# 06_-_Audio_In-Out.net
KiCad netlist of a schematic drawn in Altium Designer
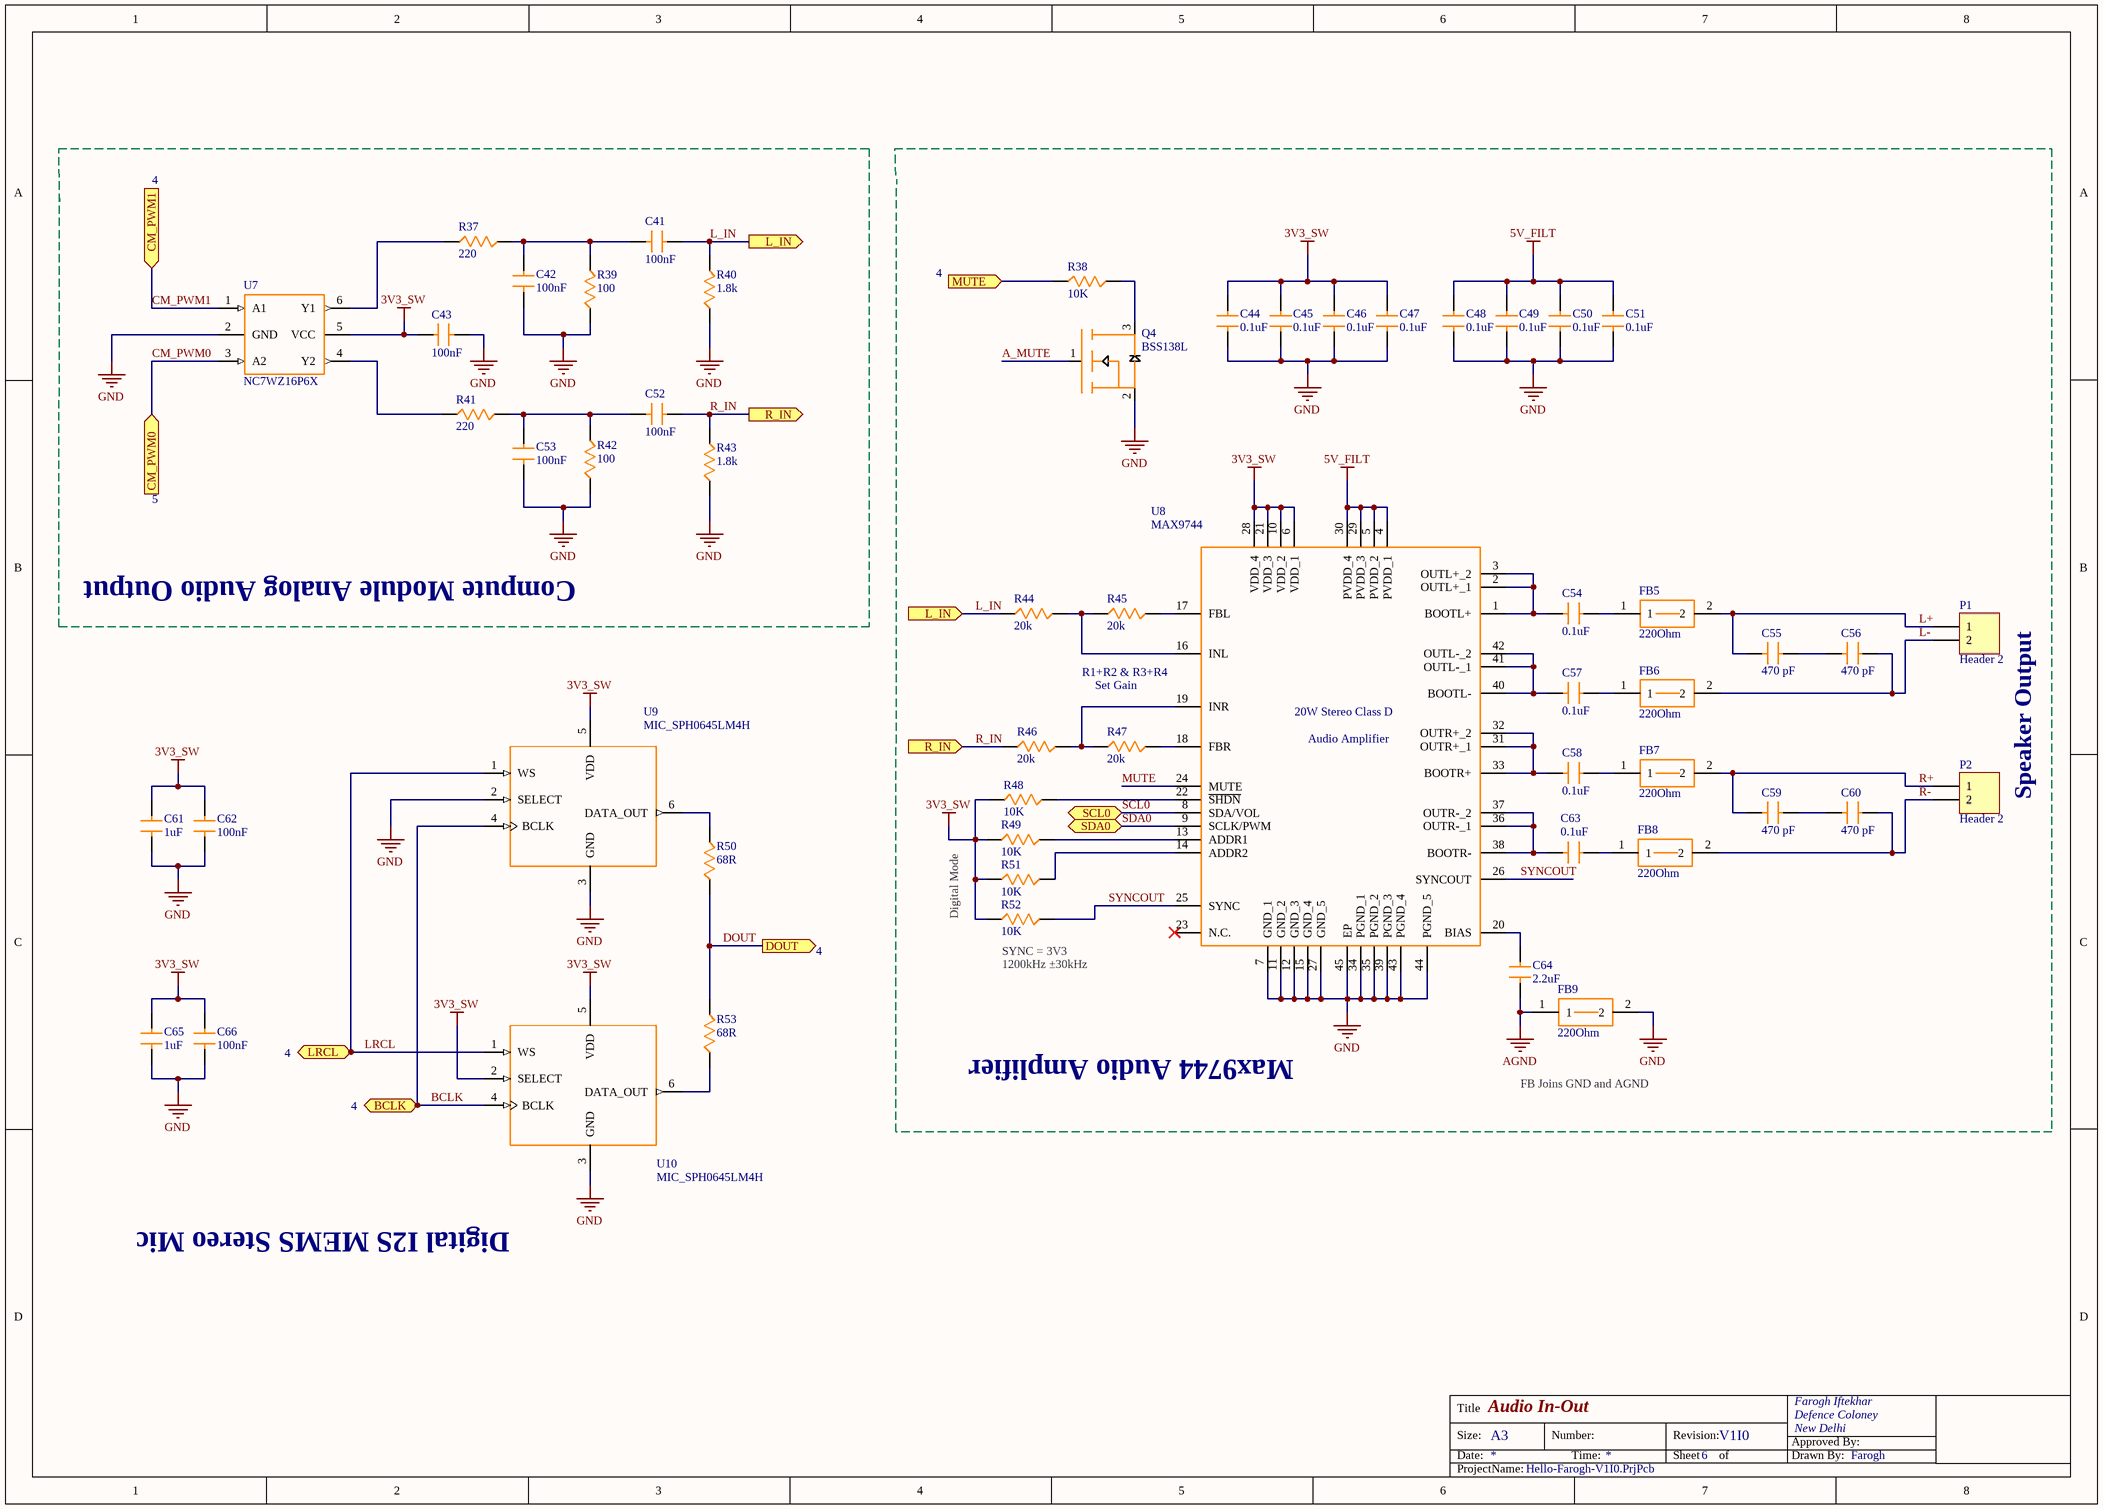
[diagram p0: [06] - Audio In-Out.SchDoc]

(export (version "E")
  (design (tool "Eeschema 10.0.6"))
  (components
    (comp (ref "C41")
      (value "100nF")
      (footprint "C0805")
      (description "Multilayer Ceramic Capacitors MLCC - SMD/SMT 100nF 16V 20% Ceramic Capacitor")
      (fields
        (field (name "MANUFACTURER") "Yageo")
        (field (name "MANUFACTURER PART NUMBER") "CC0805MRX7R7BB104")
      )
      (libsource (lib "Joule_Library") (part "C_0805-100nF-16V"))
    )
    (comp (ref "C42")
      (value "100nF")
      (footprint "C0805")
      (description "Multilayer Ceramic Capacitors MLCC - SMD/SMT 100nF 16V 20% Ceramic Capacitor")
      (fields
        (field (name "MANUFACTURER") "Yageo")
        (field (name "MANUFACTURER PART NUMBER") "CC0805MRX7R7BB104")
      )
      (libsource (lib "Joule_Library") (part "C_0805-100nF-16V"))
    )
    (comp (ref "C43")
      (value "100nF")
      (footprint "C0805")
      (description "Multilayer Ceramic Capacitors MLCC - SMD/SMT 100nF 16V 20% Ceramic Capacitor")
      (fields
        (field (name "MANUFACTURER") "Yageo")
        (field (name "MANUFACTURER PART NUMBER") "CC0805MRX7R7BB104")
      )
      (libsource (lib "Joule_Library") (part "C_0805-100nF-16V"))
    )
    (comp (ref "C44")
      (value "0.1uF")
      (footprint "C0805")
      (description "Multilayer Ceramic Capacitors MLCC - SMD/SMT 0.1uF 10% 50V AEC-Q200")
      (fields
        (field (name "MANUFACTURER") "Yageo")
        (field (name "MANUFACTURER PART NUMBER") "AS0805KKX7R9BB104")
      )
      (libsource (lib "Joule_Library") (part "C_0805-0.1uF"))
    )
    (comp (ref "C45")
      (value "0.1uF")
      (footprint "C0805")
      (description "Multilayer Ceramic Capacitors MLCC - SMD/SMT 0.1uF 10% 50V AEC-Q200")
      (fields
        (field (name "MANUFACTURER") "Yageo")
        (field (name "MANUFACTURER PART NUMBER") "AS0805KKX7R9BB104")
      )
      (libsource (lib "Joule_Library") (part "C_0805-0.1uF"))
    )
    (comp (ref "C46")
      (value "0.1uF")
      (footprint "C0805")
      (description "Multilayer Ceramic Capacitors MLCC - SMD/SMT 0.1uF 10% 50V AEC-Q200")
      (fields
        (field (name "MANUFACTURER") "Yageo")
        (field (name "MANUFACTURER PART NUMBER") "AS0805KKX7R9BB104")
      )
      (libsource (lib "Joule_Library") (part "C_0805-0.1uF"))
    )
    (comp (ref "C47")
      (value "0.1uF")
      (footprint "C0805")
      (description "Multilayer Ceramic Capacitors MLCC - SMD/SMT 0.1uF 10% 50V AEC-Q200")
      (fields
        (field (name "MANUFACTURER") "Yageo")
        (field (name "MANUFACTURER PART NUMBER") "AS0805KKX7R9BB104")
      )
      (libsource (lib "Joule_Library") (part "C_0805-0.1uF"))
    )
    (comp (ref "C48")
      (value "0.1uF")
      (footprint "C0805")
      (description "Multilayer Ceramic Capacitors MLCC - SMD/SMT 0.1uF 10% 50V AEC-Q200")
      (fields
        (field (name "MANUFACTURER") "Yageo")
        (field (name "MANUFACTURER PART NUMBER") "AS0805KKX7R9BB104")
      )
      (libsource (lib "Joule_Library") (part "C_0805-0.1uF"))
    )
    (comp (ref "C49")
      (value "0.1uF")
      (footprint "C0805")
      (description "Multilayer Ceramic Capacitors MLCC - SMD/SMT 0.1uF 10% 50V AEC-Q200")
      (fields
        (field (name "MANUFACTURER") "Yageo")
        (field (name "MANUFACTURER PART NUMBER") "AS0805KKX7R9BB104")
      )
      (libsource (lib "Joule_Library") (part "C_0805-0.1uF"))
    )
    (comp (ref "C50")
      (value "0.1uF")
      (footprint "C0805")
      (description "Multilayer Ceramic Capacitors MLCC - SMD/SMT 0.1uF 10% 50V AEC-Q200")
      (fields
        (field (name "MANUFACTURER") "Yageo")
        (field (name "MANUFACTURER PART NUMBER") "AS0805KKX7R9BB104")
      )
      (libsource (lib "Joule_Library") (part "C_0805-0.1uF"))
    )
    (comp (ref "C51")
      (value "0.1uF")
      (footprint "C0805")
      (description "Multilayer Ceramic Capacitors MLCC - SMD/SMT 0.1uF 10% 50V AEC-Q200")
      (fields
        (field (name "MANUFACTURER") "Yageo")
        (field (name "MANUFACTURER PART NUMBER") "AS0805KKX7R9BB104")
      )
      (libsource (lib "Joule_Library") (part "C_0805-0.1uF"))
    )
    (comp (ref "C52")
      (value "100nF")
      (footprint "C0805")
      (description "Multilayer Ceramic Capacitors MLCC - SMD/SMT 100nF 16V 20% Ceramic Capacitor")
      (fields
        (field (name "MANUFACTURER") "Yageo")
        (field (name "MANUFACTURER PART NUMBER") "CC0805MRX7R7BB104")
      )
      (libsource (lib "Joule_Library") (part "C_0805-100nF-16V"))
    )
    (comp (ref "C53")
      (value "100nF")
      (footprint "C0805")
      (description "Multilayer Ceramic Capacitors MLCC - SMD/SMT 100nF 16V 20% Ceramic Capacitor")
      (fields
        (field (name "MANUFACTURER") "Yageo")
        (field (name "MANUFACTURER PART NUMBER") "CC0805MRX7R7BB104")
      )
      (libsource (lib "Joule_Library") (part "C_0805-100nF-16V"))
    )
    (comp (ref "C54")
      (value "0.1uF")
      (footprint "C0805")
      (description "Multilayer Ceramic Capacitors MLCC - SMD/SMT 0.1uF 10% 50V AEC-Q200")
      (fields
        (field (name "MANUFACTURER") "Yageo")
        (field (name "MANUFACTURER PART NUMBER") "AS0805KKX7R9BB104")
      )
      (libsource (lib "Joule_Library") (part "C_0805-0.1uF"))
    )
    (comp (ref "C55")
      (value "470 pF")
      (footprint "C0805")
      (description "Multilayer Ceramic Capacitors MLCC - SMD/SMT 50V 470pF X7R 0805 10% AEC-Q200")
      (fields
        (field (name "MANUFACTURER") "KEMET")
        (field (name "MANUFACTURER PART NUMBER") "C0805S471K5RACAUTO")
      )
      (libsource (lib "Joule_Library") (part "C_0805-470 pF"))
    )
    (comp (ref "C56")
      (value "470 pF")
      (footprint "C0805")
      (description "Multilayer Ceramic Capacitors MLCC - SMD/SMT 50V 470pF X7R 0805 10% AEC-Q200")
      (fields
        (field (name "MANUFACTURER") "KEMET")
        (field (name "MANUFACTURER PART NUMBER") "C0805S471K5RACAUTO")
      )
      (libsource (lib "Joule_Library") (part "C_0805-470 pF"))
    )
    (comp (ref "C57")
      (value "0.1uF")
      (footprint "C0805")
      (description "Multilayer Ceramic Capacitors MLCC - SMD/SMT 0.1uF 10% 50V AEC-Q200")
      (fields
        (field (name "MANUFACTURER") "Yageo")
        (field (name "MANUFACTURER PART NUMBER") "AS0805KKX7R9BB104")
      )
      (libsource (lib "Joule_Library") (part "C_0805-0.1uF"))
    )
    (comp (ref "C58")
      (value "0.1uF")
      (footprint "C0805")
      (description "Multilayer Ceramic Capacitors MLCC - SMD/SMT 0.1uF 10% 50V AEC-Q200")
      (fields
        (field (name "MANUFACTURER") "Yageo")
        (field (name "MANUFACTURER PART NUMBER") "AS0805KKX7R9BB104")
      )
      (libsource (lib "Joule_Library") (part "C_0805-0.1uF"))
    )
    (comp (ref "C59")
      (value "470 pF")
      (footprint "C0805")
      (description "Multilayer Ceramic Capacitors MLCC - SMD/SMT 50V 470pF X7R 0805 10% AEC-Q200")
      (fields
        (field (name "MANUFACTURER") "KEMET")
        (field (name "MANUFACTURER PART NUMBER") "C0805S471K5RACAUTO")
      )
      (libsource (lib "Joule_Library") (part "C_0805-470 pF"))
    )
    (comp (ref "C60")
      (value "470 pF")
      (footprint "C0805")
      (description "Multilayer Ceramic Capacitors MLCC - SMD/SMT 50V 470pF X7R 0805 10% AEC-Q200")
      (fields
        (field (name "MANUFACTURER") "KEMET")
        (field (name "MANUFACTURER PART NUMBER") "C0805S471K5RACAUTO")
      )
      (libsource (lib "Joule_Library") (part "C_0805-470 pF"))
    )
    (comp (ref "C61")
      (value "1uF")
      (footprint "C0805")
      (description "Multilayer Ceramic Capacitors MLCC - SMD/SMT 10V 1uF X7R 0805 10%")
      (fields
        (field (name "MANUFACTURER") "KEMET")
        (field (name "MANUFACTURER PART NUMBER") "C0805C105K8RAC7210")
      )
      (libsource (lib "Joule_Library") (part "C_0805-1uF"))
    )
    (comp (ref "C62")
      (value "100nF")
      (footprint "C0805")
      (description "Multilayer Ceramic Capacitors MLCC - SMD/SMT 100nF 16V 20% Ceramic Capacitor")
      (fields
        (field (name "MANUFACTURER") "Yageo")
        (field (name "MANUFACTURER PART NUMBER") "CC0805MRX7R7BB104")
      )
      (libsource (lib "Joule_Library") (part "C_0805-100nF-16V"))
    )
    (comp (ref "C63")
      (value "0.1uF")
      (footprint "C0805")
      (description "Multilayer Ceramic Capacitors MLCC - SMD/SMT 0.1uF 10% 50V AEC-Q200")
      (fields
        (field (name "MANUFACTURER") "Yageo")
        (field (name "MANUFACTURER PART NUMBER") "AS0805KKX7R9BB104")
      )
      (libsource (lib "Joule_Library") (part "C_0805-0.1uF"))
    )
    (comp (ref "C64")
      (value "2.2uF")
      (footprint "C1206")
      (description "Multilayer Ceramic Capacitors MLCC - SMD/SMT 25V 2.2uF X7R 1206 10%")
      (fields
        (field (name "MANUFACTURER") "KEMET")
        (field (name "MANUFACTURER PART NUMBER") "C1206C225K3REC7210")
      )
      (libsource (lib "Joule_Library") (part "C_1206-2.2uF"))
    )
    (comp (ref "C65")
      (value "1uF")
      (footprint "C0805")
      (description "Multilayer Ceramic Capacitors MLCC - SMD/SMT 10V 1uF X7R 0805 10%")
      (fields
        (field (name "MANUFACTURER") "KEMET")
        (field (name "MANUFACTURER PART NUMBER") "C0805C105K8RAC7210")
      )
      (libsource (lib "Joule_Library") (part "C_0805-1uF"))
    )
    (comp (ref "C66")
      (value "100nF")
      (footprint "C0805")
      (description "Multilayer Ceramic Capacitors MLCC - SMD/SMT 100nF 16V 20% Ceramic Capacitor")
      (fields
        (field (name "MANUFACTURER") "Yageo")
        (field (name "MANUFACTURER PART NUMBER") "CC0805MRX7R7BB104")
      )
      (libsource (lib "Joule_Library") (part "C_0805-100nF-16V"))
    )
    (comp (ref "FB5")
      (value "220Ohm")
      (footprint "FB_0805")
      (description "Ferrite Beads NEW MFG PN 810-MPZ2012S221AT000")
      (fields (field (name "MANUFACTURER") "TDK") (field (name "MANUFACTURER PART NUMBER") "MPZ2012S221A"))
      (libsource (lib "Joule_Library") (part "FB_0805-220, 3000mA"))
    )
    (comp (ref "FB6")
      (value "220Ohm")
      (footprint "FB_0805")
      (description "Ferrite Beads NEW MFG PN 810-MPZ2012S221AT000")
      (fields (field (name "MANUFACTURER") "TDK") (field (name "MANUFACTURER PART NUMBER") "MPZ2012S221A"))
      (libsource (lib "Joule_Library") (part "FB_0805-220, 3000mA"))
    )
    (comp (ref "FB7")
      (value "220Ohm")
      (footprint "FB_0805")
      (description "Ferrite Beads NEW MFG PN 810-MPZ2012S221AT000")
      (fields (field (name "MANUFACTURER") "TDK") (field (name "MANUFACTURER PART NUMBER") "MPZ2012S221A"))
      (libsource (lib "Joule_Library") (part "FB_0805-220, 3000mA"))
    )
    (comp (ref "FB8")
      (value "220Ohm")
      (footprint "FB_0805")
      (description "Ferrite Beads NEW MFG PN 810-MPZ2012S221AT000")
      (fields (field (name "MANUFACTURER") "TDK") (field (name "MANUFACTURER PART NUMBER") "MPZ2012S221A"))
      (libsource (lib "Joule_Library") (part "FB_0805-220, 3000mA"))
    )
    (comp (ref "FB9")
      (value "220Ohm")
      (footprint "FB_0805")
      (description "Ferrite Beads NEW MFG PN 810-MPZ2012S221AT000")
      (fields (field (name "MANUFACTURER") "TDK") (field (name "MANUFACTURER PART NUMBER") "MPZ2012S221A"))
      (libsource (lib "Joule_Library") (part "FB_0805-220, 3000mA"))
    )
    (comp (ref "P1")
      (value "Header 2")
      (footprint "HDR1X2")
      (description "Header, 2-Pin")
      (fields (field (name "PUBLISHER") "Altium Limited"))
      (libsource (lib "Miscellaneous Connectors") (part "Header 2"))
    )
    (comp (ref "P2")
      (value "Header 2")
      (footprint "HDR1X2")
      (description "Header, 2-Pin")
      (fields (field (name "PUBLISHER") "Altium Limited"))
      (libsource (lib "Miscellaneous Connectors") (part "Header 2"))
    )
    (comp (ref "Q4")
      (value "BSS138L")
      (footprint "BVSS138L")
      (description "MOSFET FET 50V 3.5 OHM SOT23")
      (fields (field (name "MANUFACTURER") "ON Semiconductor / Fairchild"))
      (libsource (lib "Joule_Library") (part "BSS138L"))
    )
    (comp (ref "R37")
      (value "220")
      (footprint "R0805")
      (description "Thin Film Resistors - SMD")
      (fields
        (field (name "MANUFACTURER") "Yageo")
        (field (name "MANUFACTURER PART NUMBER") "RT0805DRE07220RL")
      )
      (libsource (lib "Joule_Library") (part "R_0805-220"))
    )
    (comp (ref "R38")
      (value "10K")
      (footprint "R0805")
      (description "Thick Film Resistors - SMD 10K   OHM   1% 1/4W")
      (fields
        (field (name "MANUFACTURER") "Yageo")
        (field (name "MANUFACTURER PART NUMBER") "RC0805FR-7W10KL")
      )
      (libsource (lib "Joule_Library") (part "R_0805-10K"))
    )
    (comp (ref "R39")
      (value "100")
      (footprint "R0805")
      (description "Thin Film Resistors - SMD 100Ohm,0805,1%,25ppm ,100mW,100V")
      (fields
        (field (name "MANUFACTURER") "KOA Speer")
        (field (name "MANUFACTURER PART NUMBER") "RN732ATTDK1000F25")
      )
      (libsource (lib "Joule_Library") (part "R_0805-100"))
    )
    (comp (ref "R40")
      (value "1.8k")
      (footprint "R0805")
      (description "Thin Film Resistors - SMD")
      (fields
        (field (name "MANUFACTURER") "Yageo")
        (field (name "MANUFACTURER PART NUMBER") "RT0805CRE071K8L")
      )
      (libsource (lib "Joule_Library") (part "R_0805-1.8K"))
    )
    (comp (ref "R41")
      (value "220")
      (footprint "R0805")
      (description "Thin Film Resistors - SMD")
      (fields
        (field (name "MANUFACTURER") "Yageo")
        (field (name "MANUFACTURER PART NUMBER") "RT0805DRE07220RL")
      )
      (libsource (lib "Joule_Library") (part "R_0805-220"))
    )
    (comp (ref "R42")
      (value "100")
      (footprint "R0805")
      (description "Thin Film Resistors - SMD 100Ohm,0805,1%,25ppm ,100mW,100V")
      (fields
        (field (name "MANUFACTURER") "KOA Speer")
        (field (name "MANUFACTURER PART NUMBER") "RN732ATTDK1000F25")
      )
      (libsource (lib "Joule_Library") (part "R_0805-100"))
    )
    (comp (ref "R43")
      (value "1.8k")
      (footprint "R0805")
      (description "Thin Film Resistors - SMD")
      (fields
        (field (name "MANUFACTURER") "Yageo")
        (field (name "MANUFACTURER PART NUMBER") "RT0805CRE071K8L")
      )
      (libsource (lib "Joule_Library") (part "R_0805-1.8K"))
    )
    (comp (ref "R44")
      (value "20k")
      (footprint "R0805")
      (description "Thin Film Resistors - SMD 20 Kohms 0.1% Tol. AEC-Q200")
      (fields
        (field (name "MANUFACTURER") "Yageo")
        (field (name "MANUFACTURER PART NUMBER") "AT0805BRD0720KL")
      )
      (libsource (lib "Joule_Library") (part "R_0805-20K"))
    )
    (comp (ref "R45")
      (value "20k")
      (footprint "R0805")
      (description "Thin Film Resistors - SMD 20 Kohms 0.1% Tol. AEC-Q200")
      (fields
        (field (name "MANUFACTURER") "Yageo")
        (field (name "MANUFACTURER PART NUMBER") "AT0805BRD0720KL")
      )
      (libsource (lib "Joule_Library") (part "R_0805-20K"))
    )
    (comp (ref "R46")
      (value "20k")
      (footprint "R0805")
      (description "Thin Film Resistors - SMD 20 Kohms 0.1% Tol. AEC-Q200")
      (fields
        (field (name "MANUFACTURER") "Yageo")
        (field (name "MANUFACTURER PART NUMBER") "AT0805BRD0720KL")
      )
      (libsource (lib "Joule_Library") (part "R_0805-20K"))
    )
    (comp (ref "R47")
      (value "20k")
      (footprint "R0805")
      (description "Thin Film Resistors - SMD 20 Kohms 0.1% Tol. AEC-Q200")
      (fields
        (field (name "MANUFACTURER") "Yageo")
        (field (name "MANUFACTURER PART NUMBER") "AT0805BRD0720KL")
      )
      (libsource (lib "Joule_Library") (part "R_0805-20K"))
    )
    (comp (ref "R48")
      (value "10K")
      (footprint "R0805")
      (description "Thick Film Resistors - SMD 10K   OHM   1% 1/4W")
      (fields
        (field (name "MANUFACTURER") "Yageo")
        (field (name "MANUFACTURER PART NUMBER") "RC0805FR-7W10KL")
      )
      (libsource (lib "Joule_Library") (part "R_0805-10K"))
    )
    (comp (ref "R49")
      (value "10K")
      (footprint "R0805")
      (description "Thick Film Resistors - SMD 10K   OHM   1% 1/4W")
      (fields
        (field (name "MANUFACTURER") "Yageo")
        (field (name "MANUFACTURER PART NUMBER") "RC0805FR-7W10KL")
      )
      (libsource (lib "Joule_Library") (part "R_0805-10K"))
    )
    (comp (ref "R50")
      (value "68R")
      (footprint "R0805")
      (description "Thick Film Resistors - SMD 1/8Watt 68ohms 1% Commercial Use")
      (fields
        (field (name "MANUFACTURER") "Vishay / Dale")
        (field (name "MANUFACTURER PART NUMBER") "CRCW080568R0FKEAC")
      )
      (libsource (lib "Joule_Library") (part "R_0805-68R"))
    )
    (comp (ref "R51")
      (value "10K")
      (footprint "R0805")
      (description "Thick Film Resistors - SMD 10K   OHM   1% 1/4W")
      (fields
        (field (name "MANUFACTURER") "Yageo")
        (field (name "MANUFACTURER PART NUMBER") "RC0805FR-7W10KL")
      )
      (libsource (lib "Joule_Library") (part "R_0805-10K"))
    )
    (comp (ref "R52")
      (value "10K")
      (footprint "R0805")
      (description "Thick Film Resistors - SMD 10K   OHM   1% 1/4W")
      (fields
        (field (name "MANUFACTURER") "Yageo")
        (field (name "MANUFACTURER PART NUMBER") "RC0805FR-7W10KL")
      )
      (libsource (lib "Joule_Library") (part "R_0805-10K"))
    )
    (comp (ref "R53")
      (value "68R")
      (footprint "R0805")
      (description "Thick Film Resistors - SMD 1/8Watt 68ohms 1% Commercial Use")
      (fields
        (field (name "MANUFACTURER") "Vishay / Dale")
        (field (name "MANUFACTURER PART NUMBER") "CRCW080568R0FKEAC")
      )
      (libsource (lib "Joule_Library") (part "R_0805-68R"))
    )
    (comp (ref "U7")
      (value "NC7WZ16P6X")
      (footprint "SOT65P210X110-6N")
      (description "Buffers & Line Drivers UHS Dual Buffer")
      (fields (field (name "MANUFACTURER") "ON Semiconductor / Fairchild"))
      (libsource (lib "Joule_Library") (part "NC7WZ16P6X"))
    )
    (comp (ref "U8")
      (value "MAX9744")
      (footprint "QFN50P700X700X80-45N")
      (description "Audio Amplifiers Stereo 20W Class D Amplifier")
      (fields
        (field (name "MANUFACTURER") "Maxim Integrated")
        (field (name "MANUFACTURER PART NUMBER") "MAX9744ETH+T")
      )
      (libsource (lib "Joule_Library") (part "MAX9744ETH+T"))
    )
    (comp (ref "U9")
      (value "MIC_SPH0645LM4H")
      (footprint "SPH0645LM4H-B")
      (description "MEMS Microphones DIG MEMs Mic, BP w/ I2S output")
      (fields
        (field (name "MANUFACTURER") "Knowles")
        (field (name "MANUFACTURER PART NUMBER") "SPH0645LM4H-B")
      )
      (libsource (lib "Joule_Library") (part "MIC_SPH0645LM4H-B"))
    )
    (comp (ref "U10")
      (value "MIC_SPH0645LM4H")
      (footprint "SPH0645LM4H-B")
      (description "MEMS Microphones DIG MEMs Mic, BP w/ I2S output")
      (fields
        (field (name "MANUFACTURER") "Knowles")
        (field (name "MANUFACTURER PART NUMBER") "SPH0645LM4H-B")
      )
      (libsource (lib "Joule_Library") (part "MIC_SPH0645LM4H-B"))
    )
  )
  (nets
    (net (code "1") (name "/A_MUTE") (class "Default")
      (node (ref "Q4") (pin "1") (pinfunction "G_1") (pintype "passive"))
    )
    (net (code "2") (name "/BCLK") (class "Default")
      (node (ref "U10") (pin "4") (pinfunction "BCLK_4") (pintype "input"))
      (node (ref "U9") (pin "4") (pinfunction "BCLK_4") (pintype "input"))
    )
    (net (code "3") (name "/CM_PWM0") (class "Default")
      (node (ref "U7") (pin "3") (pinfunction "A2_3") (pintype "input"))
    )
    (net (code "4") (name "/CM_PWM1") (class "Default")
      (node (ref "U7") (pin "1") (pinfunction "A1_1") (pintype "input"))
    )
    (net (code "5") (name "/DOUT") (class "Default")
      (node (ref "R50") (pin "1") (pinfunction "1_1") (pintype "passive"))
      (node (ref "R53") (pin "2") (pinfunction "2_2") (pintype "passive"))
    )
    (net (code "6") (name "/L+") (class "Default")
      (node (ref "C55") (pin "1") (pinfunction "1_1") (pintype "passive"))
      (node (ref "FB5") (pin "2") (pinfunction "2_2") (pintype "passive"))
      (node (ref "P1") (pin "1") (pinfunction "1_1") (pintype "passive"))
    )
    (net (code "7") (name "/L-") (class "Default")
      (node (ref "C56") (pin "2") (pinfunction "2_2") (pintype "passive"))
      (node (ref "FB6") (pin "2") (pinfunction "2_2") (pintype "passive"))
      (node (ref "P1") (pin "2") (pinfunction "2_2") (pintype "passive"))
    )
    (net (code "8") (name "/LRCL") (class "Default")
      (node (ref "U10") (pin "1") (pinfunction "WS_1") (pintype "input"))
      (node (ref "U9") (pin "1") (pinfunction "WS_1") (pintype "input"))
    )
    (net (code "9") (name "/L_IN") (class "Default")
      (node (ref "C41") (pin "2") (pinfunction "2_2") (pintype "passive"))
      (node (ref "R40") (pin "2") (pinfunction "2_2") (pintype "passive"))
      (node (ref "R44") (pin "1") (pinfunction "1_1") (pintype "passive"))
    )
    (net (code "10") (name "/MUTE") (class "Default")
      (node (ref "R38") (pin "2") (pinfunction "2_2") (pintype "passive"))
      (node (ref "U8") (pin "24") (pinfunction "MUTE_24") (pintype "passive"))
    )
    (net (code "11") (name "/R+") (class "Default")
      (node (ref "C59") (pin "1") (pinfunction "1_1") (pintype "passive"))
      (node (ref "FB7") (pin "2") (pinfunction "2_2") (pintype "passive"))
      (node (ref "P2") (pin "1") (pinfunction "1_1") (pintype "passive"))
    )
    (net (code "12") (name "/R-") (class "Default")
      (node (ref "C60") (pin "2") (pinfunction "2_2") (pintype "passive"))
      (node (ref "FB8") (pin "2") (pinfunction "2_2") (pintype "passive"))
      (node (ref "P2") (pin "2") (pinfunction "2_2") (pintype "passive"))
    )
    (net (code "13") (name "/R_IN") (class "Default")
      (node (ref "C52") (pin "2") (pinfunction "2_2") (pintype "passive"))
      (node (ref "R43") (pin "2") (pinfunction "2_2") (pintype "passive"))
      (node (ref "R46") (pin "1") (pinfunction "1_1") (pintype "passive"))
    )
    (net (code "14") (name "/SCL0") (class "Default")
      (node (ref "U8") (pin "8") (pinfunction "SDA/VOL_8") (pintype "passive"))
    )
    (net (code "15") (name "/SDA0") (class "Default")
      (node (ref "U8") (pin "9") (pinfunction "SCLK/PWM_9") (pintype "passive"))
    )
    (net (code "16") (name "/SYNCOUT") (class "Default")
      (node (ref "R52") (pin "1") (pinfunction "1_1") (pintype "passive"))
      (node (ref "U8") (pin "25") (pinfunction "SYNC_25") (pintype "passive"))
      (node (ref "U8") (pin "26") (pinfunction "SYNCOUT_26") (pintype "passive"))
    )
    (net (code "17") (name "3V3_SW") (class "Default")
      (node (ref "C43") (pin "2") (pinfunction "2_2") (pintype "passive"))
      (node (ref "C44") (pin "2") (pinfunction "2_2") (pintype "passive"))
      (node (ref "C45") (pin "2") (pinfunction "2_2") (pintype "passive"))
      (node (ref "C46") (pin "2") (pinfunction "2_2") (pintype "passive"))
      (node (ref "C47") (pin "2") (pinfunction "2_2") (pintype "passive"))
      (node (ref "C61") (pin "2") (pinfunction "2_2") (pintype "passive"))
      (node (ref "C62") (pin "2") (pinfunction "2_2") (pintype "passive"))
      (node (ref "C65") (pin "2") (pinfunction "2_2") (pintype "passive"))
      (node (ref "C66") (pin "2") (pinfunction "2_2") (pintype "passive"))
      (node (ref "R48") (pin "2") (pinfunction "2_2") (pintype "passive"))
      (node (ref "R49") (pin "2") (pinfunction "2_2") (pintype "passive"))
      (node (ref "R51") (pin "2") (pinfunction "2_2") (pintype "passive"))
      (node (ref "R52") (pin "2") (pinfunction "2_2") (pintype "passive"))
      (node (ref "U10") (pin "2") (pinfunction "SELECT_2") (pintype "input"))
      (node (ref "U10") (pin "5") (pinfunction "VDD_5") (pintype "power_in"))
      (node (ref "U7") (pin "5") (pinfunction "VCC_5") (pintype "power_in"))
      (node (ref "U8") (pin "10") (pinfunction "VDD_2_10") (pintype "passive"))
      (node (ref "U8") (pin "21") (pinfunction "VDD_3_21") (pintype "passive"))
      (node (ref "U8") (pin "28") (pinfunction "VDD_4_28") (pintype "passive"))
      (node (ref "U8") (pin "6") (pinfunction "VDD_1_6") (pintype "passive"))
      (node (ref "U9") (pin "5") (pinfunction "VDD_5") (pintype "power_in"))
    )
    (net (code "18") (name "5V_FILT") (class "Default")
      (node (ref "C48") (pin "2") (pinfunction "2_2") (pintype "passive"))
      (node (ref "C49") (pin "2") (pinfunction "2_2") (pintype "passive"))
      (node (ref "C50") (pin "2") (pinfunction "2_2") (pintype "passive"))
      (node (ref "C51") (pin "2") (pinfunction "2_2") (pintype "passive"))
      (node (ref "U8") (pin "29") (pinfunction "PVDD_3_29") (pintype "passive"))
      (node (ref "U8") (pin "30") (pinfunction "PVDD_4_30") (pintype "passive"))
      (node (ref "U8") (pin "4") (pinfunction "PVDD_1_4") (pintype "passive"))
      (node (ref "U8") (pin "5") (pinfunction "PVDD_2_5") (pintype "passive"))
    )
    (net (code "19") (name "AGND") (class "Default")
      (node (ref "C64") (pin "1") (pinfunction "1_1") (pintype "passive"))
      (node (ref "FB9") (pin "1") (pinfunction "1_1") (pintype "passive"))
    )
    (net (code "20") (name "GND") (class "Default")
      (node (ref "C42") (pin "1") (pinfunction "1_1") (pintype "passive"))
      (node (ref "C43") (pin "1") (pinfunction "1_1") (pintype "passive"))
      (node (ref "C44") (pin "1") (pinfunction "1_1") (pintype "passive"))
      (node (ref "C45") (pin "1") (pinfunction "1_1") (pintype "passive"))
      (node (ref "C46") (pin "1") (pinfunction "1_1") (pintype "passive"))
      (node (ref "C47") (pin "1") (pinfunction "1_1") (pintype "passive"))
      (node (ref "C48") (pin "1") (pinfunction "1_1") (pintype "passive"))
      (node (ref "C49") (pin "1") (pinfunction "1_1") (pintype "passive"))
      (node (ref "C50") (pin "1") (pinfunction "1_1") (pintype "passive"))
      (node (ref "C51") (pin "1") (pinfunction "1_1") (pintype "passive"))
      (node (ref "C53") (pin "1") (pinfunction "1_1") (pintype "passive"))
      (node (ref "C61") (pin "1") (pinfunction "1_1") (pintype "passive"))
      (node (ref "C62") (pin "1") (pinfunction "1_1") (pintype "passive"))
      (node (ref "C65") (pin "1") (pinfunction "1_1") (pintype "passive"))
      (node (ref "C66") (pin "1") (pinfunction "1_1") (pintype "passive"))
      (node (ref "FB9") (pin "2") (pinfunction "2_2") (pintype "passive"))
      (node (ref "Q4") (pin "2") (pinfunction "S_2") (pintype "passive"))
      (node (ref "R39") (pin "1") (pinfunction "1_1") (pintype "passive"))
      (node (ref "R40") (pin "1") (pinfunction "1_1") (pintype "passive"))
      (node (ref "R42") (pin "1") (pinfunction "1_1") (pintype "passive"))
      (node (ref "R43") (pin "1") (pinfunction "1_1") (pintype "passive"))
      (node (ref "U10") (pin "3") (pinfunction "GND_3") (pintype "power_in"))
      (node (ref "U7") (pin "2") (pinfunction "GND_2") (pintype "power_in"))
      (node (ref "U8") (pin "11") (pinfunction "GND_2_11") (pintype "passive"))
      (node (ref "U8") (pin "12") (pinfunction "GND_3_12") (pintype "passive"))
      (node (ref "U8") (pin "15") (pinfunction "GND_4_15") (pintype "passive"))
      (node (ref "U8") (pin "27") (pinfunction "GND_5_27") (pintype "passive"))
      (node (ref "U8") (pin "34") (pinfunction "PGND_1_34") (pintype "passive"))
      (node (ref "U8") (pin "35") (pinfunction "PGND_2_35") (pintype "passive"))
      (node (ref "U8") (pin "39") (pinfunction "PGND_3_39") (pintype "passive"))
      (node (ref "U8") (pin "43") (pinfunction "PGND_4_43") (pintype "passive"))
      (node (ref "U8") (pin "44") (pinfunction "PGND_5_44") (pintype "passive"))
      (node (ref "U8") (pin "45") (pinfunction "EP_45") (pintype "passive"))
      (node (ref "U8") (pin "7") (pinfunction "GND_1_7") (pintype "passive"))
      (node (ref "U9") (pin "2") (pinfunction "SELECT_2") (pintype "input"))
      (node (ref "U9") (pin "3") (pinfunction "GND_3") (pintype "power_in"))
    )
    (net (code "21") (name "Net-(C41-Pad1)") (class "Default")
      (node (ref "C41") (pin "1") (pinfunction "1_1") (pintype "passive"))
      (node (ref "C42") (pin "2") (pinfunction "2_2") (pintype "passive"))
      (node (ref "R37") (pin "2") (pinfunction "2_2") (pintype "passive"))
      (node (ref "R39") (pin "2") (pinfunction "2_2") (pintype "passive"))
    )
    (net (code "22") (name "Net-(C52-Pad1)") (class "Default")
      (node (ref "C52") (pin "1") (pinfunction "1_1") (pintype "passive"))
      (node (ref "C53") (pin "2") (pinfunction "2_2") (pintype "passive"))
      (node (ref "R41") (pin "2") (pinfunction "2_2") (pintype "passive"))
      (node (ref "R42") (pin "2") (pinfunction "2_2") (pintype "passive"))
    )
    (net (code "23") (name "Net-(C54-Pad2)") (class "Default")
      (node (ref "C54") (pin "2") (pinfunction "2_2") (pintype "passive"))
      (node (ref "FB5") (pin "1") (pinfunction "1_1") (pintype "passive"))
    )
    (net (code "24") (name "Net-(C55-Pad2)") (class "Default")
      (node (ref "C55") (pin "2") (pinfunction "2_2") (pintype "passive"))
      (node (ref "C56") (pin "1") (pinfunction "1_1") (pintype "passive"))
    )
    (net (code "25") (name "Net-(C57-Pad2)") (class "Default")
      (node (ref "C57") (pin "2") (pinfunction "2_2") (pintype "passive"))
      (node (ref "FB6") (pin "1") (pinfunction "1_1") (pintype "passive"))
    )
    (net (code "26") (name "Net-(C58-Pad2)") (class "Default")
      (node (ref "C58") (pin "2") (pinfunction "2_2") (pintype "passive"))
      (node (ref "FB7") (pin "1") (pinfunction "1_1") (pintype "passive"))
    )
    (net (code "27") (name "Net-(C59-Pad2)") (class "Default")
      (node (ref "C59") (pin "2") (pinfunction "2_2") (pintype "passive"))
      (node (ref "C60") (pin "1") (pinfunction "1_1") (pintype "passive"))
    )
    (net (code "28") (name "Net-(C63-Pad2)") (class "Default")
      (node (ref "C63") (pin "2") (pinfunction "2_2") (pintype "passive"))
      (node (ref "FB8") (pin "1") (pinfunction "1_1") (pintype "passive"))
    )
    (net (code "29") (name "Net-(Q4-D)") (class "Default")
      (node (ref "Q4") (pin "3") (pinfunction "D_3") (pintype "passive"))
      (node (ref "R38") (pin "1") (pinfunction "1_1") (pintype "passive"))
    )
    (net (code "30") (name "Net-(U7-Y1)") (class "Default")
      (node (ref "R37") (pin "1") (pinfunction "1_1") (pintype "passive"))
      (node (ref "U7") (pin "6") (pinfunction "Y1_6") (pintype "output"))
    )
    (net (code "31") (name "Net-(U7-Y2)") (class "Default")
      (node (ref "R41") (pin "1") (pinfunction "1_1") (pintype "passive"))
      (node (ref "U7") (pin "4") (pinfunction "Y2_4") (pintype "output"))
    )
    (net (code "32") (name "Net-(U8-ADDR1)") (class "Default")
      (node (ref "R49") (pin "1") (pinfunction "1_1") (pintype "passive"))
      (node (ref "U8") (pin "13") (pinfunction "ADDR1_13") (pintype "passive"))
    )
    (net (code "33") (name "Net-(U8-ADDR2)") (class "Default")
      (node (ref "R51") (pin "1") (pinfunction "1_1") (pintype "passive"))
      (node (ref "U8") (pin "14") (pinfunction "ADDR2_14") (pintype "passive"))
    )
    (net (code "34") (name "Net-(U8-BIAS)") (class "Default")
      (node (ref "C64") (pin "2") (pinfunction "2_2") (pintype "passive"))
      (node (ref "U8") (pin "20") (pinfunction "BIAS_20") (pintype "passive"))
    )
    (net (code "35") (name "Net-(U8-BOOTL+)") (class "Default")
      (node (ref "C54") (pin "1") (pinfunction "1_1") (pintype "passive"))
      (node (ref "U8") (pin "1") (pinfunction "BOOTL+_1") (pintype "passive"))
      (node (ref "U8") (pin "2") (pinfunction "OUTL+_1_2") (pintype "passive"))
      (node (ref "U8") (pin "3") (pinfunction "OUTL+_2_3") (pintype "passive"))
    )
    (net (code "36") (name "Net-(U8-BOOTL-)") (class "Default")
      (node (ref "C57") (pin "1") (pinfunction "1_1") (pintype "passive"))
      (node (ref "U8") (pin "40") (pinfunction "BOOTL-_40") (pintype "passive"))
      (node (ref "U8") (pin "41") (pinfunction "OUTL-_1_41") (pintype "passive"))
      (node (ref "U8") (pin "42") (pinfunction "OUTL-_2_42") (pintype "passive"))
    )
    (net (code "37") (name "Net-(U8-BOOTR+)") (class "Default")
      (node (ref "C58") (pin "1") (pinfunction "1_1") (pintype "passive"))
      (node (ref "U8") (pin "31") (pinfunction "OUTR+_1_31") (pintype "passive"))
      (node (ref "U8") (pin "32") (pinfunction "OUTR+_2_32") (pintype "passive"))
      (node (ref "U8") (pin "33") (pinfunction "BOOTR+_33") (pintype "passive"))
    )
    (net (code "38") (name "Net-(U8-BOOTR-)") (class "Default")
      (node (ref "C63") (pin "1") (pinfunction "1_1") (pintype "passive"))
      (node (ref "U8") (pin "36") (pinfunction "OUTR-_1_36") (pintype "passive"))
      (node (ref "U8") (pin "37") (pinfunction "OUTR-_2_37") (pintype "passive"))
      (node (ref "U8") (pin "38") (pinfunction "BOOTR-_38") (pintype "passive"))
    )
    (net (code "39") (name "Net-(U8-FBL)") (class "Default")
      (node (ref "R45") (pin "2") (pinfunction "2_2") (pintype "passive"))
      (node (ref "U8") (pin "17") (pinfunction "FBL_17") (pintype "passive"))
    )
    (net (code "40") (name "Net-(U8-FBR)") (class "Default")
      (node (ref "R47") (pin "2") (pinfunction "2_2") (pintype "passive"))
      (node (ref "U8") (pin "18") (pinfunction "FBR_18") (pintype "passive"))
    )
    (net (code "41") (name "Net-(U8-INL)") (class "Default")
      (node (ref "R44") (pin "2") (pinfunction "2_2") (pintype "passive"))
      (node (ref "R45") (pin "1") (pinfunction "1_1") (pintype "passive"))
      (node (ref "U8") (pin "16") (pinfunction "INL_16") (pintype "passive"))
    )
    (net (code "42") (name "Net-(U8-INR)") (class "Default")
      (node (ref "R46") (pin "2") (pinfunction "2_2") (pintype "passive"))
      (node (ref "R47") (pin "1") (pinfunction "1_1") (pintype "passive"))
      (node (ref "U8") (pin "19") (pinfunction "INR_19") (pintype "passive"))
    )
    (net (code "43") (name "Net-(U8-~{SHDN})") (class "Default")
      (node (ref "R48") (pin "1") (pinfunction "1_1") (pintype "passive"))
      (node (ref "U8") (pin "22") (pinfunction "~{SHDN}_22") (pintype "passive"))
    )
    (net (code "44") (name "Net-(U9-DATA_OUT)") (class "Default")
      (node (ref "R50") (pin "2") (pinfunction "2_2") (pintype "passive"))
      (node (ref "U9") (pin "6") (pinfunction "DATA_OUT_6") (pintype "output"))
    )
    (net (code "45") (name "Net-(U10-DATA_OUT)") (class "Default")
      (node (ref "R53") (pin "1") (pinfunction "1_1") (pintype "passive"))
      (node (ref "U10") (pin "6") (pinfunction "DATA_OUT_6") (pintype "output"))
    )
    (net (code "46") (name "unconnected-(U8-N.C.-Pad23)") (class "Default")
      (node (ref "U8") (pin "23") (pinfunction "N.C._23") (pintype "passive+no_connect"))
    )
  )
)
